# SCH_Recovery-Heltec-Nakuja_2022-10-19.net
KiCad netlist of a schematic drawn in EasyEDA
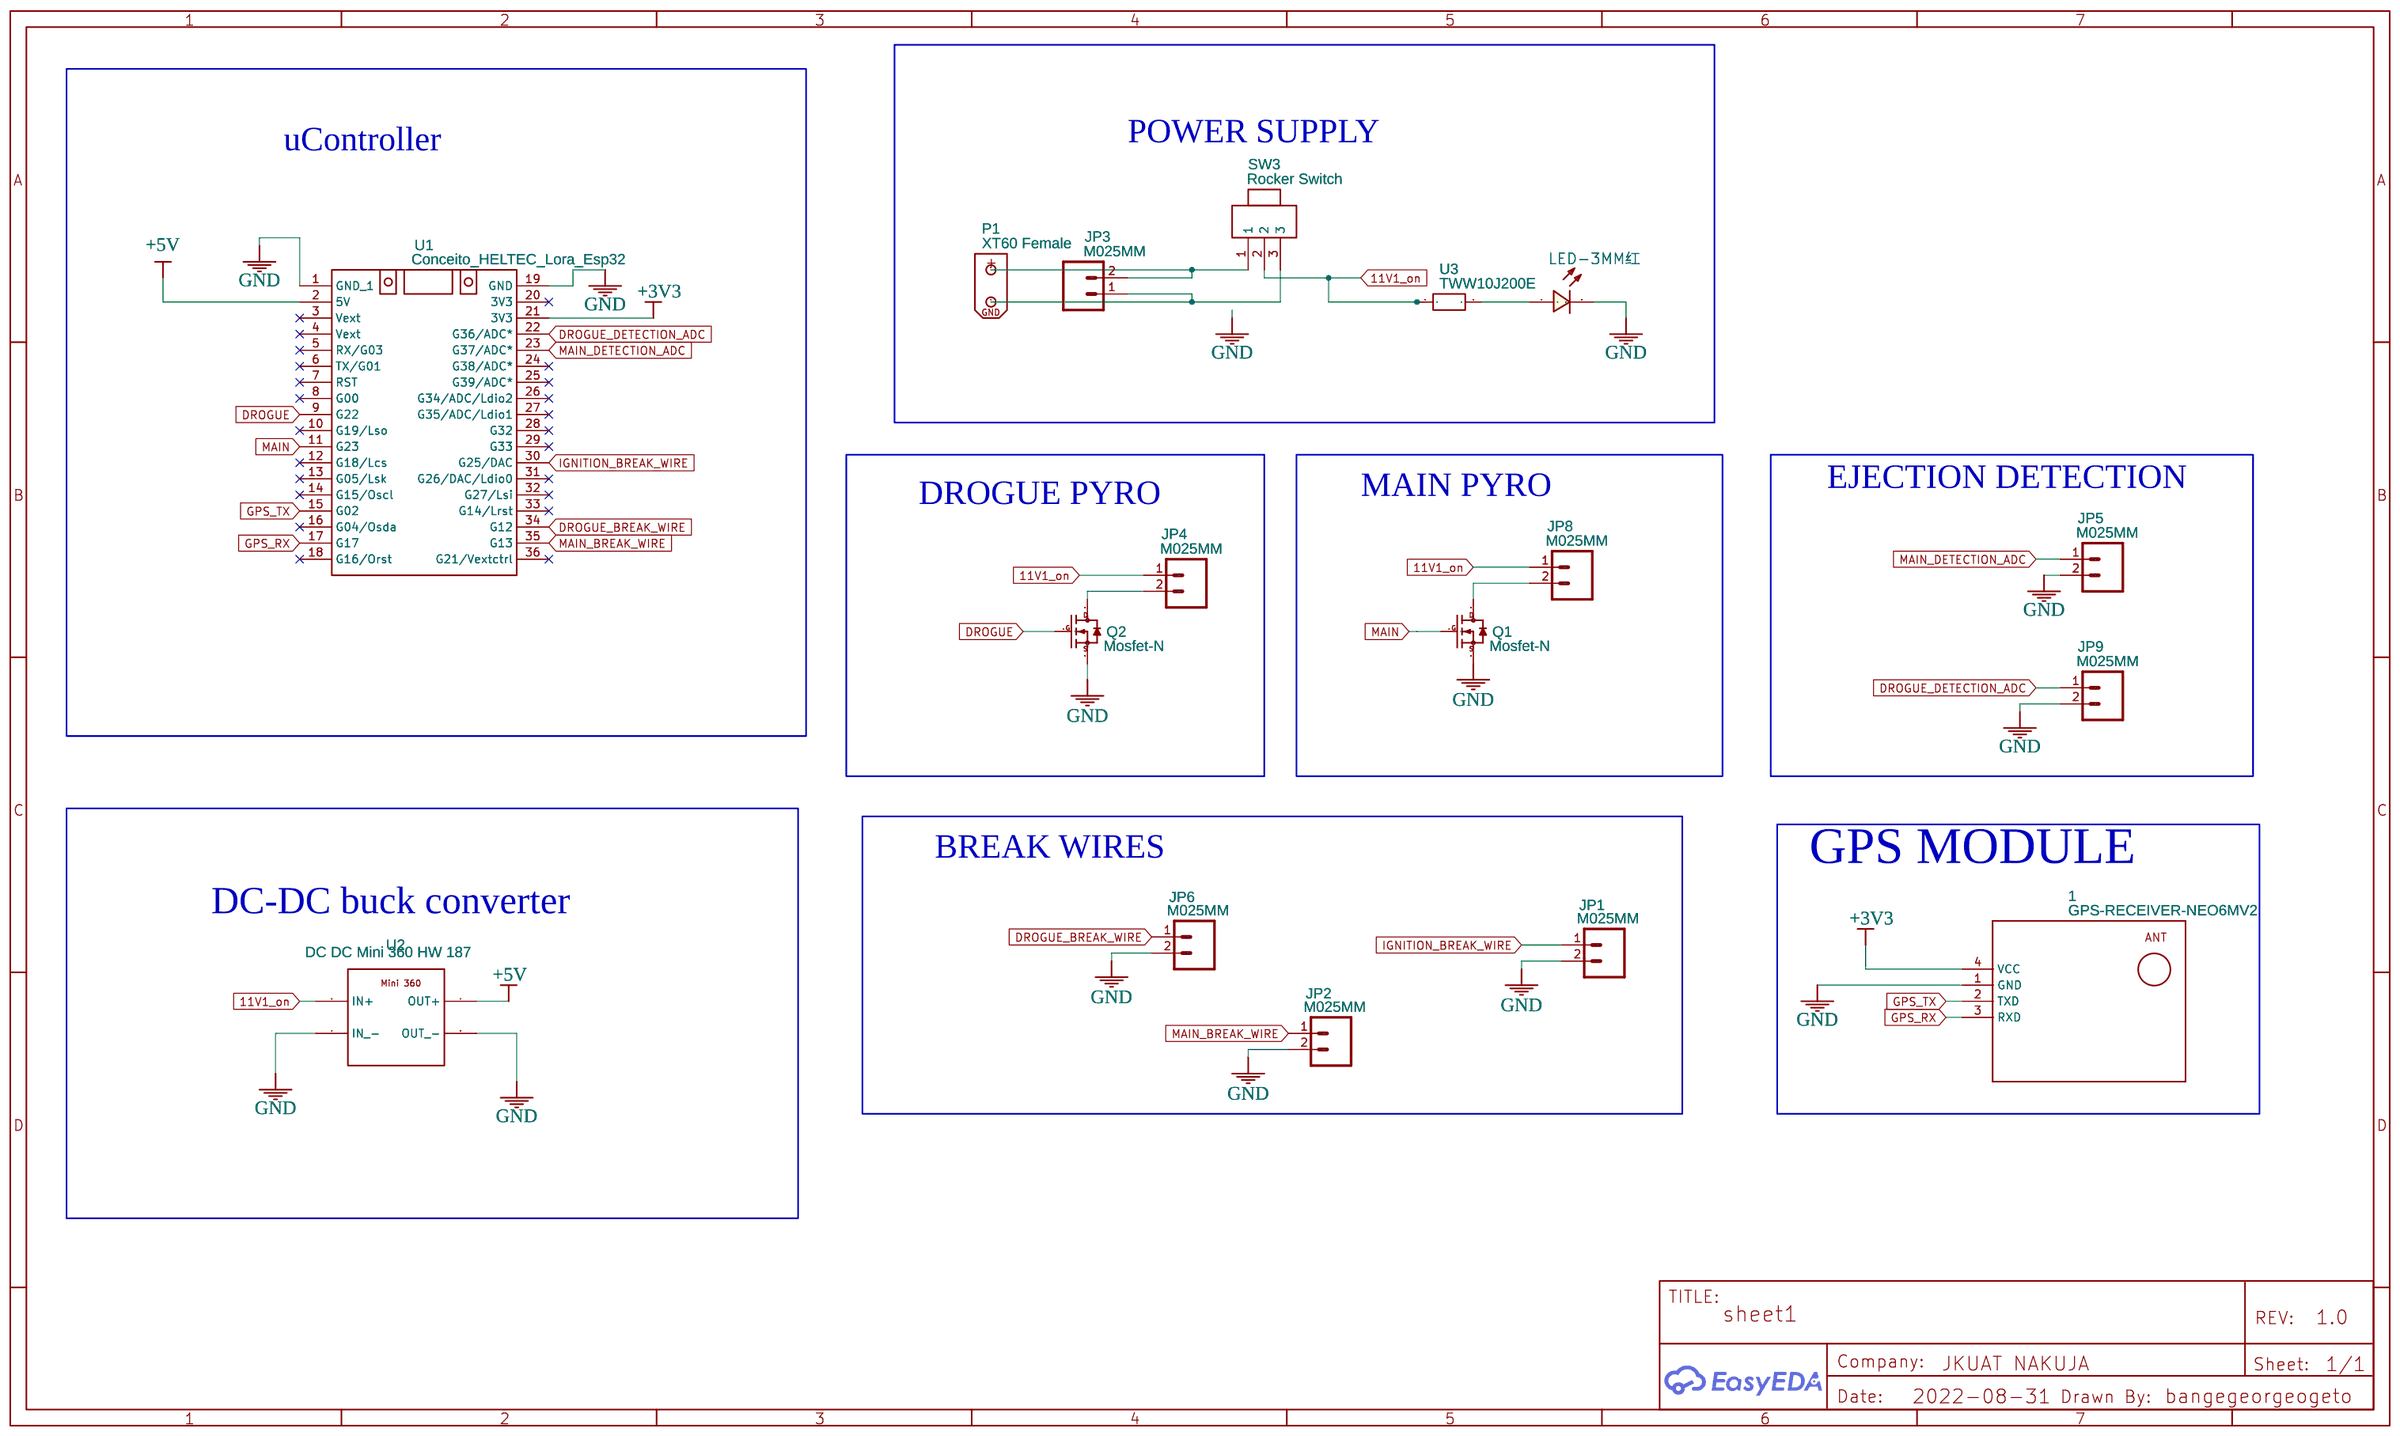
[diagram p0: schematic sheet]

(export (version "E")
  (design (tool "Eeschema 10.0.6"))
  (components
    (comp (ref "1") (value "GPS-RECEIVER-NEO6MV2") (libsource (lib "") (part "GPS-RECEIVER-NEO6MV2")))
    (comp (ref "JP1") (value "M025MM") (libsource (lib "") (part "M025MM")))
    (comp (ref "JP2") (value "M025MM") (libsource (lib "") (part "M025MM")))
    (comp (ref "JP3") (value "M025MM") (libsource (lib "") (part "M025MM_1")))
    (comp (ref "JP4") (value "M025MM") (libsource (lib "") (part "M025MM")))
    (comp (ref "JP5") (value "M025MM") (libsource (lib "") (part "M025MM")))
    (comp (ref "JP6") (value "M025MM") (libsource (lib "") (part "M025MM")))
    (comp (ref "JP8") (value "M025MM") (libsource (lib "") (part "M025MM")))
    (comp (ref "JP9") (value "M025MM") (libsource (lib "") (part "M025MM")))
    (comp (ref "NO")
      (value "LED-3MM红")
      (fields
        (field (name "BOM_Manufacturer Part") "LED-3mm红")
        (field (name "BOM_Supplier Part") "C9900003389")
      )
      (libsource (lib "") (part "LED-3MM红"))
    )
    (comp (ref "P1")
      (value "XT60 Female")
      (fields (field (name "BOM_Manufacturer Part") "XT60-F"))
      (libsource (lib "") (part "XT60 Female"))
    )
    (comp (ref "Q1") (value "Mosfet-N") (libsource (lib "") (part "Mosfet-N")))
    (comp (ref "Q2") (value "Mosfet-N") (libsource (lib "") (part "Mosfet-N")))
    (comp (ref "SW3") (value "Rocker Switch") (libsource (lib "") (part "Rocker Switch")))
    (comp (ref "U1")
      (value "Conceito_HELTEC_Lora_Esp32")
      (libsource (lib "") (part "Conceito_HELTEC_Lora_Esp32"))
    )
    (comp (ref "U2") (value "DC DC Mini 360 HW 187") (libsource (lib "") (part "DC DC Mini 360 HW 187")))
    (comp (ref "U3")
      (value "TWW10J200E")
      (fields (field (name "BOM_Supplier Part") "C3353311"))
      (libsource (lib "") (part "TWW10J200E"))
    )
  )
  (nets
    (net (code "1") (name "+3V3") (class "Default")
      (node (ref "1") (pin "4") (pinfunction "VCC_4") (pintype "bidirectional"))
      (node (ref "U1") (pin "21") (pinfunction "3V3_21") (pintype "bidirectional"))
    )
    (net (code "2") (name "+5V") (class "Default")
      (node (ref "U1") (pin "2") (pinfunction "5V_2") (pintype "bidirectional"))
      (node (ref "U2") (pin "1") (pinfunction "OUT+_1") (pintype "unspecified"))
    )
    (net (code "3") (name "11V1_on") (class "Default")
      (node (ref "JP4") (pin "1") (pinfunction "1_1") (pintype "bidirectional"))
      (node (ref "JP8") (pin "1") (pinfunction "1_1") (pintype "bidirectional"))
      (node (ref "SW3") (pin "2") (pinfunction "2_2") (pintype "unspecified"))
      (node (ref "U2") (pin "3") (pinfunction "IN+_3") (pintype "unspecified"))
      (node (ref "U3") (pin "1") (pinfunction "1_1") (pintype "unspecified"))
    )
    (net (code "4") (name "DROGUE") (class "Default")
      (node (ref "Q2") (pin "1") (pinfunction "G_1") (pintype "unspecified"))
      (node (ref "U1") (pin "9") (pinfunction "G22_9") (pintype "bidirectional"))
    )
    (net (code "5") (name "DROGUE_BREAK_WIRE") (class "Default")
      (node (ref "JP6") (pin "1") (pinfunction "1_1") (pintype "bidirectional"))
      (node (ref "U1") (pin "34") (pinfunction "G12_34") (pintype "bidirectional"))
    )
    (net (code "6") (name "DROGUE_DETECTION_ADC") (class "Default")
      (node (ref "JP9") (pin "1") (pinfunction "1_1") (pintype "bidirectional"))
      (node (ref "U1") (pin "22") (pinfunction "G36/ADC*_22") (pintype "input"))
    )
    (net (code "7") (name "GND") (class "Default")
      (node (ref "1") (pin "1") (pinfunction "GND_1") (pintype "bidirectional"))
      (node (ref "JP1") (pin "2") (pinfunction "2_2") (pintype "bidirectional"))
      (node (ref "JP2") (pin "2") (pinfunction "2_2") (pintype "bidirectional"))
      (node (ref "JP5") (pin "2") (pinfunction "2_2") (pintype "bidirectional"))
      (node (ref "JP6") (pin "2") (pinfunction "2_2") (pintype "bidirectional"))
      (node (ref "JP9") (pin "2") (pinfunction "2_2") (pintype "bidirectional"))
      (node (ref "NO") (pin "2") (pinfunction "2_2") (pintype "unspecified"))
      (node (ref "Q1") (pin "3") (pinfunction "S_3") (pintype "unspecified"))
      (node (ref "Q2") (pin "3") (pinfunction "S_3") (pintype "unspecified"))
      (node (ref "U1") (pin "1") (pinfunction "GND_1_1") (pintype "bidirectional"))
      (node (ref "U1") (pin "19") (pinfunction "GND_19") (pintype "bidirectional"))
      (node (ref "U2") (pin "2") (pinfunction "OUT_-_2") (pintype "unspecified"))
      (node (ref "U2") (pin "4") (pinfunction "IN_-_4") (pintype "unspecified"))
    )
    (net (code "8") (name "GPS_RX") (class "Default")
      (node (ref "1") (pin "3") (pinfunction "RXD_3") (pintype "bidirectional"))
      (node (ref "U1") (pin "17") (pinfunction "G17_17") (pintype "bidirectional"))
    )
    (net (code "9") (name "GPS_TX") (class "Default")
      (node (ref "1") (pin "2") (pinfunction "TXD_2") (pintype "bidirectional"))
      (node (ref "U1") (pin "15") (pinfunction "G02_15") (pintype "bidirectional"))
    )
    (net (code "10") (name "IGNITION_BREAK_WIRE") (class "Default")
      (node (ref "JP1") (pin "1") (pinfunction "1_1") (pintype "bidirectional"))
      (node (ref "U1") (pin "30") (pinfunction "G25/DAC_30") (pintype "bidirectional"))
    )
    (net (code "11") (name "MAIN") (class "Default")
      (node (ref "Q1") (pin "1") (pinfunction "G_1") (pintype "unspecified"))
      (node (ref "U1") (pin "11") (pinfunction "G23_11") (pintype "bidirectional"))
    )
    (net (code "12") (name "MAIN_BREAK_WIRE") (class "Default")
      (node (ref "JP2") (pin "1") (pinfunction "1_1") (pintype "bidirectional"))
      (node (ref "U1") (pin "35") (pinfunction "G13_35") (pintype "bidirectional"))
    )
    (net (code "13") (name "MAIN_DETECTION_ADC") (class "Default")
      (node (ref "JP5") (pin "1") (pinfunction "1_1") (pintype "bidirectional"))
      (node (ref "U1") (pin "23") (pinfunction "G37/ADC*_23") (pintype "input"))
    )
    (net (code "14") (name "Net-(JP3-Pad1)") (class "Default")
      (node (ref "JP3") (pin "1") (pinfunction "1_1") (pintype "bidirectional"))
      (node (ref "P1") (pin "1") (pinfunction "1_1") (pintype "unspecified"))
      (node (ref "SW3") (pin "3") (pinfunction "3_3") (pintype "unspecified"))
    )
    (net (code "15") (name "Net-(JP3-Pad2)") (class "Default")
      (node (ref "JP3") (pin "2") (pinfunction "2_2") (pintype "bidirectional"))
      (node (ref "P1") (pin "2") (pinfunction "2_2") (pintype "unspecified"))
      (node (ref "SW3") (pin "1") (pinfunction "1_1") (pintype "unspecified"))
    )
    (net (code "16") (name "Net-(NO-Pad1)") (class "Default")
      (node (ref "NO") (pin "1") (pinfunction "1_1") (pintype "unspecified"))
      (node (ref "U3") (pin "2") (pinfunction "2_2") (pintype "unspecified"))
    )
    (net (code "17") (name "Net-(Q1-D)") (class "Default")
      (node (ref "JP8") (pin "2") (pinfunction "2_2") (pintype "bidirectional"))
      (node (ref "Q1") (pin "2") (pinfunction "D_2") (pintype "unspecified"))
    )
    (net (code "18") (name "Net-(Q2-D)") (class "Default")
      (node (ref "JP4") (pin "2") (pinfunction "2_2") (pintype "bidirectional"))
      (node (ref "Q2") (pin "2") (pinfunction "D_2") (pintype "unspecified"))
    )
    (net (code "19") (name "unconnected-(U1-3V3-Pad20)") (class "Default")
      (node (ref "U1") (pin "20") (pinfunction "3V3_20") (pintype "bidirectional+no_connect"))
    )
    (net (code "20") (name "unconnected-(U1-G00-Pad8)") (class "Default")
      (node (ref "U1") (pin "8") (pinfunction "G00_8") (pintype "bidirectional+no_connect"))
    )
    (net (code "21") (name "unconnected-(U1-G04{slash}Osda-Pad16)") (class "Default")
      (node (ref "U1") (pin "16") (pinfunction "G04/Osda_16") (pintype "bidirectional+no_connect"))
    )
    (net (code "22") (name "unconnected-(U1-G05{slash}Lsk-Pad13)") (class "Default")
      (node (ref "U1") (pin "13") (pinfunction "G05/Lsk_13") (pintype "bidirectional+no_connect"))
    )
    (net (code "23") (name "unconnected-(U1-G14{slash}Lrst-Pad33)") (class "Default")
      (node (ref "U1") (pin "33") (pinfunction "G14/Lrst_33") (pintype "bidirectional+no_connect"))
    )
    (net (code "24") (name "unconnected-(U1-G15{slash}Oscl-Pad14)") (class "Default")
      (node (ref "U1") (pin "14") (pinfunction "G15/Oscl_14") (pintype "bidirectional+no_connect"))
    )
    (net (code "25") (name "unconnected-(U1-G16{slash}Orst-Pad18)") (class "Default")
      (node (ref "U1") (pin "18") (pinfunction "G16/Orst_18") (pintype "bidirectional+no_connect"))
    )
    (net (code "26") (name "unconnected-(U1-G18{slash}Lcs-Pad12)") (class "Default")
      (node (ref "U1") (pin "12") (pinfunction "G18/Lcs_12") (pintype "bidirectional+no_connect"))
    )
    (net (code "27") (name "unconnected-(U1-G19{slash}Lso-Pad10)") (class "Default")
      (node (ref "U1") (pin "10") (pinfunction "G19/Lso_10") (pintype "bidirectional+no_connect"))
    )
    (net (code "28") (name "unconnected-(U1-G21{slash}Vextctrl-Pad36)") (class "Default")
      (node (ref "U1") (pin "36") (pinfunction "G21/Vextctrl_36") (pintype "bidirectional+no_connect"))
    )
    (net (code "29") (name "unconnected-(U1-G26{slash}DAC{slash}Ldio0-Pad31)") (class "Default")
      (node (ref "U1") (pin "31") (pinfunction "G26/DAC/Ldio0_31") (pintype "bidirectional+no_connect"))
    )
    (net (code "30") (name "unconnected-(U1-G27{slash}Lsi-Pad32)") (class "Default")
      (node (ref "U1") (pin "32") (pinfunction "G27/Lsi_32") (pintype "bidirectional+no_connect"))
    )
    (net (code "31") (name "unconnected-(U1-G32-Pad28)") (class "Default")
      (node (ref "U1") (pin "28") (pinfunction "G32_28") (pintype "input+no_connect"))
    )
    (net (code "32") (name "unconnected-(U1-G33-Pad29)") (class "Default")
      (node (ref "U1") (pin "29") (pinfunction "G33_29") (pintype "input+no_connect"))
    )
    (net (code "33") (name "unconnected-(U1-G34{slash}ADC{slash}Ldio2-Pad26)") (class "Default")
      (node (ref "U1") (pin "26") (pinfunction "G34/ADC/Ldio2_26") (pintype "input+no_connect"))
    )
    (net (code "34") (name "unconnected-(U1-G35{slash}ADC{slash}Ldio1-Pad27)") (class "Default")
      (node (ref "U1") (pin "27") (pinfunction "G35/ADC/Ldio1_27") (pintype "input+no_connect"))
    )
    (net (code "35") (name "unconnected-(U1-G38{slash}ADC*-Pad24)") (class "Default")
      (node (ref "U1") (pin "24") (pinfunction "G38/ADC*_24") (pintype "input+no_connect"))
    )
    (net (code "36") (name "unconnected-(U1-G39{slash}ADC*-Pad25)") (class "Default")
      (node (ref "U1") (pin "25") (pinfunction "G39/ADC*_25") (pintype "input+no_connect"))
    )
    (net (code "37") (name "unconnected-(U1-RST-Pad7)") (class "Default")
      (node (ref "U1") (pin "7") (pinfunction "RST_7") (pintype "bidirectional+no_connect"))
    )
    (net (code "38") (name "unconnected-(U1-RX{slash}G03-Pad5)") (class "Default")
      (node (ref "U1") (pin "5") (pinfunction "RX/G03_5") (pintype "bidirectional+no_connect"))
    )
    (net (code "39") (name "unconnected-(U1-TX{slash}G01-Pad6)") (class "Default")
      (node (ref "U1") (pin "6") (pinfunction "TX/G01_6") (pintype "bidirectional+no_connect"))
    )
    (net (code "40") (name "unconnected-(U1-Vext-Pad3)") (class "Default")
      (node (ref "U1") (pin "3") (pinfunction "Vext_3") (pintype "bidirectional+no_connect"))
    )
    (net (code "41") (name "unconnected-(U1-Vext-Pad4)") (class "Default")
      (node (ref "U1") (pin "4") (pinfunction "Vext_4") (pintype "bidirectional+no_connect"))
    )
  )
)
